# NOR_GATE.net
KiCad netlist of a schematic drawn in Altium Designer
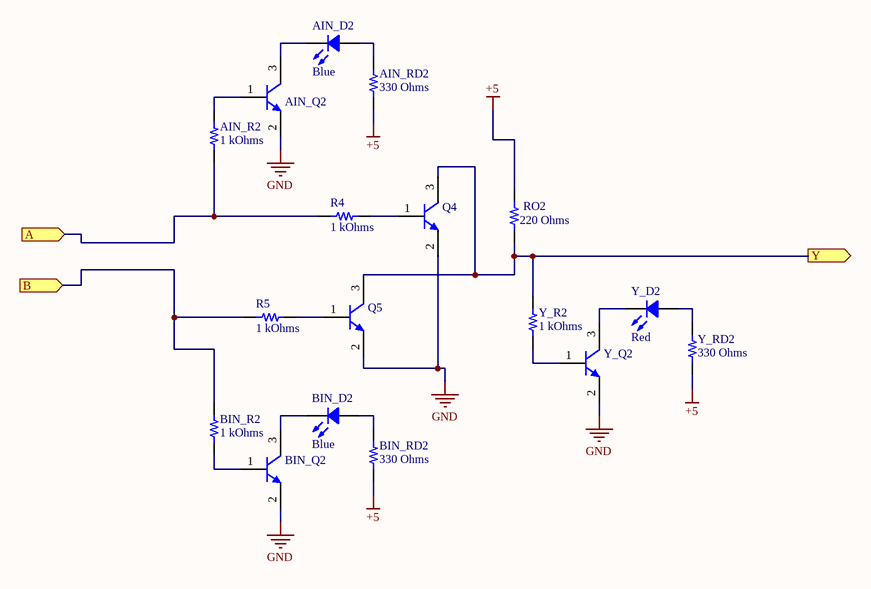
[diagram p0: NOR_GATE.SchDoc]

(export (version "E")
  (design (tool "Eeschema 10.0.6"))
  (components
    (comp (ref "AIN_D2")
      (value "Blue")
      (footprint "LED 0603_1608 BLUE")
      (description "LED BLUE CLEAR 0603 SMD")
      (fields (field (name "PART NUMBER") "IN-S63AT5B") (field (name "MANUFACTURER") "Inolux"))
      (libsource (lib "Celestial Altium Library - altium_library") (part "LED"))
    )
    (comp (ref "AIN_Q2")
      (value "MMSS8050-L-TP")
      (footprint "MCCSEMI SOT-23-3")
      (description "TRANS NPN 25V 1.5A SOT23")
      (fields (field (name "MANUFACTURER") "Micro Commercial Co"))
      (libsource (lib "Celestial Altium Library - altium_library") (part "MCCSEMI NPN SOT-23-3"))
    )
    (comp (ref "AIN_R2")
      (value "1 kOhms")
      (footprint "RES 0603_1608")
      (description "RES SMD 1K OHM 0.1% 1/16W 0603")
      (fields
        (field (name "PART NUMBER") "CPF0603B1K0E")
        (field (name "MANUFACTURER") "TE Connectivity Passive Product")
      )
      (libsource (lib "Celestial Altium Library - altium_library") (part "Resistor"))
    )
    (comp (ref "AIN_RD2")
      (value "330 Ohms")
      (footprint "RES 0603_1608")
      (description "RES 330 OHM 5% 1/10W 0603")
      (fields
        (field (name "PART NUMBER") "RMCF0603JT330R")
        (field (name "MANUFACTURER") "Stackpole Electronics Inc")
      )
      (libsource (lib "Celestial Altium Library - altium_library") (part "Resistor"))
    )
    (comp (ref "BIN_D2")
      (value "Blue")
      (footprint "LED 0603_1608 BLUE")
      (description "LED BLUE CLEAR 0603 SMD")
      (fields (field (name "PART NUMBER") "IN-S63AT5B") (field (name "MANUFACTURER") "Inolux"))
      (libsource (lib "Celestial Altium Library - altium_library") (part "LED"))
    )
    (comp (ref "BIN_Q2")
      (value "MMSS8050-L-TP")
      (footprint "MCCSEMI SOT-23-3")
      (description "TRANS NPN 25V 1.5A SOT23")
      (fields (field (name "MANUFACTURER") "Micro Commercial Co"))
      (libsource (lib "Celestial Altium Library - altium_library") (part "MCCSEMI NPN SOT-23-3"))
    )
    (comp (ref "BIN_R2")
      (value "1 kOhms")
      (footprint "RES 0603_1608")
      (description "RES SMD 1K OHM 0.1% 1/16W 0603")
      (fields
        (field (name "PART NUMBER") "CPF0603B1K0E")
        (field (name "MANUFACTURER") "TE Connectivity Passive Product")
      )
      (libsource (lib "Celestial Altium Library - altium_library") (part "Resistor"))
    )
    (comp (ref "BIN_RD2")
      (value "330 Ohms")
      (footprint "RES 0603_1608")
      (description "RES 330 OHM 5% 1/10W 0603")
      (fields
        (field (name "PART NUMBER") "RMCF0603JT330R")
        (field (name "MANUFACTURER") "Stackpole Electronics Inc")
      )
      (libsource (lib "Celestial Altium Library - altium_library") (part "Resistor"))
    )
    (comp (ref "Q4")
      (value "MMSS8050-L-TP")
      (footprint "MCCSEMI SOT-23-3")
      (description "TRANS NPN 25V 1.5A SOT23")
      (fields (field (name "MANUFACTURER") "Micro Commercial Co"))
      (libsource (lib "Celestial Altium Library - altium_library") (part "MCCSEMI NPN SOT-23-3"))
    )
    (comp (ref "Q5")
      (value "MMSS8050-L-TP")
      (footprint "MCCSEMI SOT-23-3")
      (description "TRANS NPN 25V 1.5A SOT23")
      (fields (field (name "MANUFACTURER") "Micro Commercial Co"))
      (libsource (lib "Celestial Altium Library - altium_library") (part "MCCSEMI NPN SOT-23-3"))
    )
    (comp (ref "R4")
      (value "1 kOhms")
      (footprint "RES 0603_1608")
      (description "RES SMD 1K OHM 0.1% 1/16W 0603")
      (fields
        (field (name "PART NUMBER") "CPF0603B1K0E")
        (field (name "MANUFACTURER") "TE Connectivity Passive Product")
      )
      (libsource (lib "Celestial Altium Library - altium_library") (part "Resistor"))
    )
    (comp (ref "R5")
      (value "1 kOhms")
      (footprint "RES 0603_1608")
      (description "RES SMD 1K OHM 0.1% 1/16W 0603")
      (fields
        (field (name "PART NUMBER") "CPF0603B1K0E")
        (field (name "MANUFACTURER") "TE Connectivity Passive Product")
      )
      (libsource (lib "Celestial Altium Library - altium_library") (part "Resistor"))
    )
    (comp (ref "RO2")
      (value "220 Ohms")
      (footprint "RES 0603_1608")
      (description "RES SMD 220 OHM 0.5% 1/10W 0603")
      (fields
        (field (name "PART NUMBER") "ERA-3AED221V")
        (field (name "MANUFACTURER") "Panasonic Electronic Components")
      )
      (libsource (lib "Celestial Altium Library - altium_library") (part "Resistor"))
    )
    (comp (ref "Y_D2")
      (value "Red")
      (footprint "LED 0603_1608 RED")
      (description "LED RED CLEAR CHIP SMD")
      (fields (field (name "PART NUMBER") "XZMDK53W-8") (field (name "MANUFACTURER") "SunLED"))
      (libsource (lib "Celestial Altium Library - altium_library") (part "LED"))
    )
    (comp (ref "Y_Q2")
      (value "MMSS8050-L-TP")
      (footprint "MCCSEMI SOT-23-3")
      (description "TRANS NPN 25V 1.5A SOT23")
      (fields (field (name "MANUFACTURER") "Micro Commercial Co"))
      (libsource (lib "Celestial Altium Library - altium_library") (part "MCCSEMI NPN SOT-23-3"))
    )
    (comp (ref "Y_R2")
      (value "1 kOhms")
      (footprint "RES 0603_1608")
      (description "RES SMD 1K OHM 0.1% 1/16W 0603")
      (fields
        (field (name "PART NUMBER") "CPF0603B1K0E")
        (field (name "MANUFACTURER") "TE Connectivity Passive Product")
      )
      (libsource (lib "Celestial Altium Library - altium_library") (part "Resistor"))
    )
    (comp (ref "Y_RD2")
      (value "330 Ohms")
      (footprint "RES 0603_1608")
      (description "RES 330 OHM 5% 1/10W 0603")
      (fields
        (field (name "PART NUMBER") "RMCF0603JT330R")
        (field (name "MANUFACTURER") "Stackpole Electronics Inc")
      )
      (libsource (lib "Celestial Altium Library - altium_library") (part "Resistor"))
    )
  )
  (nets
    (net (code "1") (name "+5") (class "Default")
      (node (ref "AIN_RD2") (pin "1") (pinfunction "1_1") (pintype "passive"))
      (node (ref "BIN_RD2") (pin "1") (pinfunction "1_1") (pintype "passive"))
      (node (ref "RO2") (pin "2") (pinfunction "2_2") (pintype "passive"))
      (node (ref "Y_RD2") (pin "1") (pinfunction "1_1") (pintype "passive"))
    )
    (net (code "2") (name "/A") (class "Default")
      (node (ref "AIN_R2") (pin "2") (pinfunction "2_2") (pintype "passive"))
      (node (ref "R4") (pin "1") (pinfunction "1_1") (pintype "passive"))
    )
    (net (code "3") (name "/B") (class "Default")
      (node (ref "BIN_R2") (pin "2") (pinfunction "2_2") (pintype "passive"))
      (node (ref "R5") (pin "1") (pinfunction "1_1") (pintype "passive"))
    )
    (net (code "4") (name "/Y") (class "Default")
      (node (ref "Q4") (pin "3") (pinfunction "C_3") (pintype "passive"))
      (node (ref "Q5") (pin "3") (pinfunction "C_3") (pintype "passive"))
      (node (ref "RO2") (pin "1") (pinfunction "1_1") (pintype "passive"))
      (node (ref "Y_R2") (pin "2") (pinfunction "2_2") (pintype "passive"))
    )
    (net (code "5") (name "GND") (class "Default")
      (node (ref "AIN_Q2") (pin "2") (pinfunction "E_2") (pintype "passive"))
      (node (ref "BIN_Q2") (pin "2") (pinfunction "E_2") (pintype "passive"))
      (node (ref "Q4") (pin "2") (pinfunction "E_2") (pintype "passive"))
      (node (ref "Q5") (pin "2") (pinfunction "E_2") (pintype "passive"))
      (node (ref "Y_Q2") (pin "2") (pinfunction "E_2") (pintype "passive"))
    )
    (net (code "6") (name "Net-(AIN_D2-Pad1)") (class "Default")
      (node (ref "AIN_D2") (pin "1") (pinfunction "1_1") (pintype "passive"))
      (node (ref "AIN_RD2") (pin "2") (pinfunction "2_2") (pintype "passive"))
    )
    (net (code "7") (name "Net-(AIN_Q2-B)") (class "Default")
      (node (ref "AIN_Q2") (pin "1") (pinfunction "B_1") (pintype "passive"))
      (node (ref "AIN_R2") (pin "1") (pinfunction "1_1") (pintype "passive"))
    )
    (net (code "8") (name "Net-(AIN_Q2-C)") (class "Default")
      (node (ref "AIN_D2") (pin "2") (pinfunction "2_2") (pintype "passive"))
      (node (ref "AIN_Q2") (pin "3") (pinfunction "C_3") (pintype "passive"))
    )
    (net (code "9") (name "Net-(BIN_D2-Pad1)") (class "Default")
      (node (ref "BIN_D2") (pin "1") (pinfunction "1_1") (pintype "passive"))
      (node (ref "BIN_RD2") (pin "2") (pinfunction "2_2") (pintype "passive"))
    )
    (net (code "10") (name "Net-(BIN_Q2-B)") (class "Default")
      (node (ref "BIN_Q2") (pin "1") (pinfunction "B_1") (pintype "passive"))
      (node (ref "BIN_R2") (pin "1") (pinfunction "1_1") (pintype "passive"))
    )
    (net (code "11") (name "Net-(BIN_Q2-C)") (class "Default")
      (node (ref "BIN_D2") (pin "2") (pinfunction "2_2") (pintype "passive"))
      (node (ref "BIN_Q2") (pin "3") (pinfunction "C_3") (pintype "passive"))
    )
    (net (code "12") (name "Net-(Q4-B)") (class "Default")
      (node (ref "Q4") (pin "1") (pinfunction "B_1") (pintype "passive"))
      (node (ref "R4") (pin "2") (pinfunction "2_2") (pintype "passive"))
    )
    (net (code "13") (name "Net-(Q5-B)") (class "Default")
      (node (ref "Q5") (pin "1") (pinfunction "B_1") (pintype "passive"))
      (node (ref "R5") (pin "2") (pinfunction "2_2") (pintype "passive"))
    )
    (net (code "14") (name "Net-(Y_D2-Pad1)") (class "Default")
      (node (ref "Y_D2") (pin "1") (pinfunction "1_1") (pintype "passive"))
      (node (ref "Y_RD2") (pin "2") (pinfunction "2_2") (pintype "passive"))
    )
    (net (code "15") (name "Net-(Y_Q2-B)") (class "Default")
      (node (ref "Y_Q2") (pin "1") (pinfunction "B_1") (pintype "passive"))
      (node (ref "Y_R2") (pin "1") (pinfunction "1_1") (pintype "passive"))
    )
    (net (code "16") (name "Net-(Y_Q2-C)") (class "Default")
      (node (ref "Y_D2") (pin "2") (pinfunction "2_2") (pintype "passive"))
      (node (ref "Y_Q2") (pin "3") (pinfunction "C_3") (pintype "passive"))
    )
  )
)
